# Arduino.net
KiCad netlist of a schematic drawn in Altium Designer
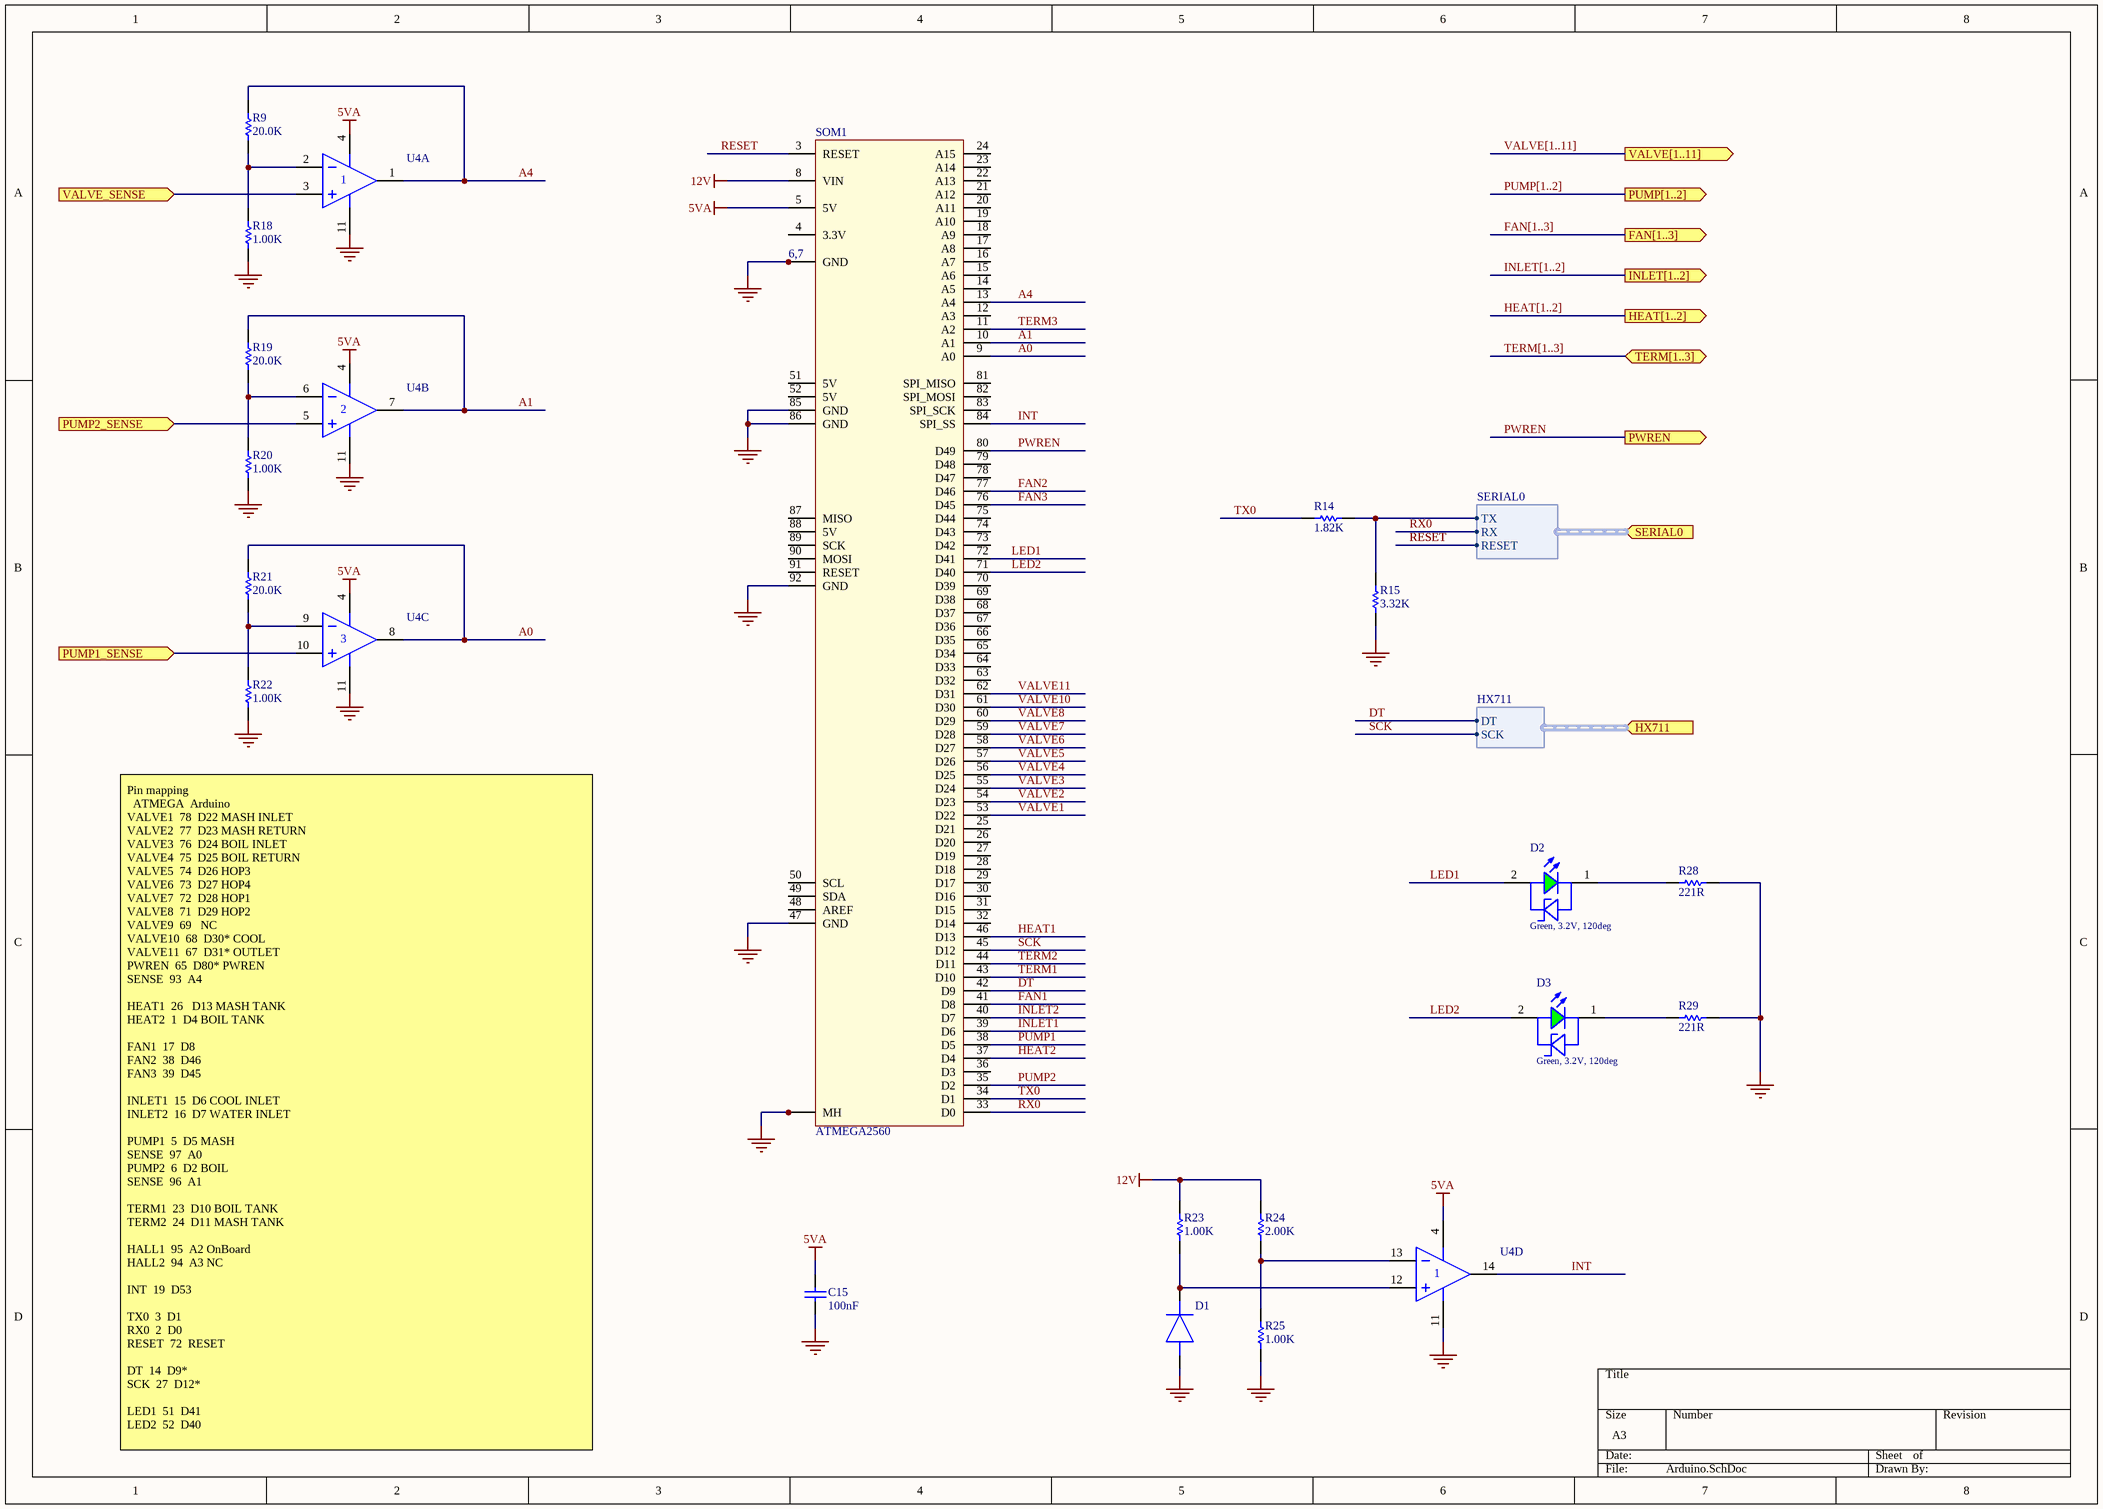
[diagram p0: Arduino.SchDoc]

(export (version "E")
  (design (tool "Eeschema 10.0.6"))
  (components
    (comp (ref "C15")
      (value "100nF")
      (footprint "CAP_0603_H090 (_IPC_MD)")
      (description "CAP CER 100NF 50V X7R 0603")
      (fields (field (name "PART NUMBER") "CL10B104KB8NNNC") (field (name "Comment") "100nF 0603"))
      (libsource (lib "MUAB_Altium_Lib") (part "CAP"))
    )
    (comp (ref "D1")
      (value "LL4148-GS18")
      (footprint "OpenBrewie:SOD-80")
      (description "Diode")
      (fields (field (name "MOUSER PART NUMBER") "78-LL4148-GS18"))
      (libsource (lib "OpenBrewie") (part "LL4148-GS18"))
    )
    (comp (ref "D2")
      (value "Green, 3.2V, 120deg")
      (footprint "WL-SMCC_0603_GS_BS")
      (description "WL-SMCC SMD Mono-color Chip LED Compact, size 0603, Green, 3.2V, 120deg")
      (fields (field (name "PART NUMBER") "150060GS73220") (field (name "PUBLISHER") "Wurth Elektronik"))
      (libsource (lib "Altium_WL-SMCC (rev19a)") (part "150060GS73220"))
    )
    (comp (ref "D3")
      (value "Green, 3.2V, 120deg")
      (footprint "WL-SMCC_0603_GS_BS")
      (description "WL-SMCC SMD Mono-color Chip LED Compact, size 0603, Green, 3.2V, 120deg")
      (fields (field (name "PART NUMBER") "150060GS73220") (field (name "PUBLISHER") "Wurth Elektronik"))
      (libsource (lib "Altium_WL-SMCC (rev19a)") (part "150060GS73220"))
    )
    (comp (ref "R9")
      (value "20.0K")
      (footprint "RES_0603_H050 (_IPC_MD)")
      (description "20.0K 1% 0,1W 75V 0603")
      (fields (field (name "PART NUMBER") "RES20.0K1%0603"))
      (libsource (lib "MUAB_Altium_Lib") (part "RES"))
    )
    (comp (ref "R14")
      (value "1.82K")
      (footprint "RES_0603_H050 (_IPC_MD)")
      (description "1.82K 1% 0,1W 75V 0603")
      (fields (field (name "PART NUMBER") "RES1.82K1%0603"))
      (libsource (lib "MUAB_Altium_Lib") (part "RES"))
    )
    (comp (ref "R15")
      (value "3.32K")
      (footprint "RES_0603_H050 (_IPC_MD)")
      (description "3.32K 1% 0,1W 75V 0603")
      (fields (field (name "PART NUMBER") "RES3.32K1%0603"))
      (libsource (lib "MUAB_Altium_Lib") (part "RES"))
    )
    (comp (ref "R18")
      (value "1.00K")
      (footprint "RES_0603_H050 (_IPC_MD)")
      (description "1.00K 1% 0,1W 75V 0603")
      (fields (field (name "PART NUMBER") "RES1.00K1%0603"))
      (libsource (lib "MUAB_Altium_Lib") (part "RES"))
    )
    (comp (ref "R19")
      (value "20.0K")
      (footprint "RES_0603_H050 (_IPC_MD)")
      (description "20.0K 1% 0,1W 75V 0603")
      (fields (field (name "PART NUMBER") "RES20.0K1%0603"))
      (libsource (lib "MUAB_Altium_Lib") (part "RES"))
    )
    (comp (ref "R20")
      (value "1.00K")
      (footprint "RES_0603_H050 (_IPC_MD)")
      (description "1.00K 1% 0,1W 75V 0603")
      (fields (field (name "PART NUMBER") "RES1.00K1%0603"))
      (libsource (lib "MUAB_Altium_Lib") (part "RES"))
    )
    (comp (ref "R21")
      (value "20.0K")
      (footprint "RES_0603_H050 (_IPC_MD)")
      (description "20.0K 1% 0,1W 75V 0603")
      (fields (field (name "PART NUMBER") "RES20.0K1%0603"))
      (libsource (lib "MUAB_Altium_Lib") (part "RES"))
    )
    (comp (ref "R22")
      (value "1.00K")
      (footprint "RES_0603_H050 (_IPC_MD)")
      (description "1.00K 1% 0,1W 75V 0603")
      (fields (field (name "PART NUMBER") "RES1.00K1%0603"))
      (libsource (lib "MUAB_Altium_Lib") (part "RES"))
    )
    (comp (ref "R23")
      (value "1.00K")
      (footprint "RES_0603_H050 (_IPC_MD)")
      (description "1.00K 1% 0,1W 75V 0603")
      (fields (field (name "PART NUMBER") "RES1.00K1%0603"))
      (libsource (lib "MUAB_Altium_Lib") (part "RES"))
    )
    (comp (ref "R24")
      (value "2.00K")
      (footprint "RES_0603_H050 (_IPC_MD)")
      (description "2.00K 1% 0,1W 75V 0603")
      (fields (field (name "PART NUMBER") "RES2.00K1%0603"))
      (libsource (lib "MUAB_Altium_Lib") (part "RES"))
    )
    (comp (ref "R25")
      (value "1.00K")
      (footprint "RES_0603_H050 (_IPC_MD)")
      (description "1.00K 1% 0,1W 75V 0603")
      (fields (field (name "PART NUMBER") "RES1.00K1%0603"))
      (libsource (lib "MUAB_Altium_Lib") (part "RES"))
    )
    (comp (ref "R28")
      (value "221R")
      (footprint "RES_0603_H050 (_IPC_MD)")
      (description "221R 1% 0,1W 75V 0603")
      (fields (field (name "PART NUMBER") "RES221R1%0603"))
      (libsource (lib "MUAB_Altium_Lib") (part "RES"))
    )
    (comp (ref "R29")
      (value "221R")
      (footprint "RES_0603_H050 (_IPC_MD)")
      (description "221R 1% 0,1W 75V 0603")
      (fields (field (name "PART NUMBER") "RES221R1%0603"))
      (libsource (lib "MUAB_Altium_Lib") (part "RES"))
    )
    (comp (ref "SOM1")
      (value "ATMEGA2560")
      (footprint "ATMEGA2560")
      (libsource (lib "OpenBrewie") (part "ATMEGA2560"))
    )
    (comp (ref "U4")
      (value "MAX4478ASD+")
      (footprint "SOIC127P600X175-14N")
      (description "IC OPAMP GP 2 CIRCUIT 8SOIC")
      (libsource (lib "MUAB_Altium_Lib") (part "MAX4478"))
    )
  )
  (nets
    (net (code "4") (name "/A0") (class "Default")
      (node (ref "R21") (pin "2") (pinfunction "2_2") (pintype "passive"))
      (node (ref "SOM1") (pin "9") (pinfunction "A0_9") (pintype "passive"))
      (node (ref "U4") (pin "8") (pinfunction "OUT3_8") (pintype "passive"))
    )
    (net (code "5") (name "/A1") (class "Default")
      (node (ref "R19") (pin "2") (pinfunction "2_2") (pintype "passive"))
      (node (ref "SOM1") (pin "10") (pinfunction "A1_10") (pintype "passive"))
      (node (ref "U4") (pin "7") (pinfunction "OUT2_7") (pintype "passive"))
    )
    (net (code "6") (name "/A4") (class "Default")
      (node (ref "R9") (pin "2") (pinfunction "2_2") (pintype "passive"))
      (node (ref "SOM1") (pin "13") (pinfunction "A4_13") (pintype "passive"))
      (node (ref "U4") (pin "1") (pinfunction "OUT1_1") (pintype "passive"))
    )
    (net (code "7") (name "/DT") (class "Default")
      (node (ref "SOM1") (pin "42") (pinfunction "D9_42") (pintype "passive"))
    )
    (net (code "8") (name "/FAN1") (class "Default")
      (node (ref "SOM1") (pin "41") (pinfunction "D8_41") (pintype "passive"))
    )
    (net (code "9") (name "/FAN2") (class "Default")
      (node (ref "SOM1") (pin "77") (pinfunction "D46_77") (pintype "passive"))
    )
    (net (code "10") (name "/FAN3") (class "Default")
      (node (ref "SOM1") (pin "76") (pinfunction "D45_76") (pintype "passive"))
    )
    (net (code "12") (name "/HEAT1") (class "Default")
      (node (ref "SOM1") (pin "46") (pinfunction "D13_46") (pintype "passive"))
    )
    (net (code "13") (name "/HEAT2") (class "Default")
      (node (ref "SOM1") (pin "37") (pinfunction "D4_37") (pintype "passive"))
    )
    (net (code "15") (name "/INLET1") (class "Default")
      (node (ref "SOM1") (pin "39") (pinfunction "D6_39") (pintype "passive"))
    )
    (net (code "16") (name "/INLET2") (class "Default")
      (node (ref "SOM1") (pin "40") (pinfunction "D7_40") (pintype "passive"))
    )
    (net (code "18") (name "/INT") (class "Default")
      (node (ref "SOM1") (pin "84") (pinfunction "SPI_SS_84") (pintype "passive"))
      (node (ref "U4") (pin "14") (pinfunction "OUT4_14") (pintype "passive"))
    )
    (net (code "19") (name "/LED1") (class "Default")
      (node (ref "D2") (pin "2") (pinfunction "A_2") (pintype "passive"))
      (node (ref "SOM1") (pin "72") (pinfunction "D41_72") (pintype "passive"))
    )
    (net (code "20") (name "/LED2") (class "Default")
      (node (ref "D3") (pin "2") (pinfunction "A_2") (pintype "passive"))
      (node (ref "SOM1") (pin "71") (pinfunction "D40_71") (pintype "passive"))
    )
    (net (code "21") (name "/PUMP1") (class "Default")
      (node (ref "SOM1") (pin "38") (pinfunction "D5_38") (pintype "passive"))
    )
    (net (code "22") (name "/PUMP1_SENSE") (class "Default")
      (node (ref "U4") (pin "10") (pinfunction "IN3+_10") (pintype "passive"))
    )
    (net (code "23") (name "/PUMP2") (class "Default")
      (node (ref "SOM1") (pin "35") (pinfunction "D2_35") (pintype "passive"))
    )
    (net (code "24") (name "/PUMP2_SENSE") (class "Default")
      (node (ref "U4") (pin "5") (pinfunction "IN2+_5") (pintype "passive"))
    )
    (net (code "26") (name "/PWREN") (class "Default")
      (node (ref "SOM1") (pin "80") (pinfunction "D49_80") (pintype "passive"))
    )
    (net (code "27") (name "/RESET") (class "Default")
      (node (ref "SOM1") (pin "3") (pinfunction "RESET_3") (pintype "passive"))
    )
    (net (code "28") (name "/RX0") (class "Default")
      (node (ref "SOM1") (pin "33") (pinfunction "D0_33") (pintype "passive"))
    )
    (net (code "29") (name "/SCK") (class "Default")
      (node (ref "SOM1") (pin "45") (pinfunction "D12_45") (pintype "passive"))
    )
    (net (code "30") (name "/TERM1") (class "Default")
      (node (ref "SOM1") (pin "43") (pinfunction "D10_43") (pintype "passive"))
    )
    (net (code "31") (name "/TERM2") (class "Default")
      (node (ref "SOM1") (pin "44") (pinfunction "D11_44") (pintype "passive"))
    )
    (net (code "32") (name "/TERM3") (class "Default")
      (node (ref "SOM1") (pin "11") (pinfunction "A2_11") (pintype "passive"))
    )
    (net (code "34") (name "/TX0") (class "Default")
      (node (ref "R14") (pin "1") (pinfunction "1_1") (pintype "passive"))
      (node (ref "SOM1") (pin "34") (pinfunction "D1_34") (pintype "passive"))
    )
    (net (code "35") (name "/VALVE1") (class "Default")
      (node (ref "SOM1") (pin "53") (pinfunction "D22_53") (pintype "passive"))
    )
    (net (code "36") (name "/VALVE2") (class "Default")
      (node (ref "SOM1") (pin "54") (pinfunction "D23_54") (pintype "passive"))
    )
    (net (code "37") (name "/VALVE3") (class "Default")
      (node (ref "SOM1") (pin "55") (pinfunction "D24_55") (pintype "passive"))
    )
    (net (code "38") (name "/VALVE4") (class "Default")
      (node (ref "SOM1") (pin "56") (pinfunction "D25_56") (pintype "passive"))
    )
    (net (code "39") (name "/VALVE5") (class "Default")
      (node (ref "SOM1") (pin "57") (pinfunction "D26_57") (pintype "passive"))
    )
    (net (code "40") (name "/VALVE6") (class "Default")
      (node (ref "SOM1") (pin "58") (pinfunction "D27_58") (pintype "passive"))
    )
    (net (code "41") (name "/VALVE7") (class "Default")
      (node (ref "SOM1") (pin "59") (pinfunction "D28_59") (pintype "passive"))
    )
    (net (code "42") (name "/VALVE8") (class "Default")
      (node (ref "SOM1") (pin "60") (pinfunction "D29_60") (pintype "passive"))
    )
    (net (code "43") (name "/VALVE10") (class "Default")
      (node (ref "SOM1") (pin "61") (pinfunction "D30_61") (pintype "passive"))
    )
    (net (code "44") (name "/VALVE11") (class "Default")
      (node (ref "SOM1") (pin "62") (pinfunction "D31_62") (pintype "passive"))
    )
    (net (code "46") (name "/VALVE_SENSE") (class "Default")
      (node (ref "U4") (pin "3") (pinfunction "IN1+_3") (pintype "passive"))
    )
    (net (code "49") (name "5VA") (class "Default")
      (node (ref "C15") (pin "1") (pinfunction "1_1") (pintype "passive"))
      (node (ref "SOM1") (pin "5") (pinfunction "5V_5") (pintype "power_in"))
      (node (ref "U4") (pin "4") (pinfunction "V+_4") (pintype "power_in"))
    )
    (net (code "50") (name "12V") (class "Default")
      (node (ref "R23") (pin "1") (pinfunction "1_1") (pintype "passive"))
      (node (ref "R24") (pin "1") (pinfunction "1_1") (pintype "passive"))
      (node (ref "SOM1") (pin "8") (pinfunction "VIN_8") (pintype "power_in"))
    )
    (net (code "51") (name "GND") (class "Default")
      (node (ref "C15") (pin "2") (pinfunction "2_2") (pintype "passive"))
      (node (ref "D1") (pin "2") (pinfunction "A_2") (pintype "passive"))
      (node (ref "R15") (pin "2") (pinfunction "2_2") (pintype "passive"))
      (node (ref "R18") (pin "1") (pinfunction "1_1") (pintype "passive"))
      (node (ref "R20") (pin "1") (pinfunction "1_1") (pintype "passive"))
      (node (ref "R22") (pin "1") (pinfunction "1_1") (pintype "passive"))
      (node (ref "R25") (pin "2") (pinfunction "2_2") (pintype "passive"))
      (node (ref "R28") (pin "2") (pinfunction "2_2") (pintype "passive"))
      (node (ref "R29") (pin "2") (pinfunction "2_2") (pintype "passive"))
      (node (ref "SOM1") (pin "47") (pinfunction "GND_47") (pintype "power_in"))
      (node (ref "SOM1") (pin "6") (pinfunction "GND_6") (pintype "power_in"))
      (node (ref "SOM1") (pin "7") (pinfunction "GND_7") (pintype "power_in"))
      (node (ref "SOM1") (pin "85") (pinfunction "GND_85") (pintype "power_in"))
      (node (ref "SOM1") (pin "86") (pinfunction "GND_86") (pintype "power_in"))
      (node (ref "SOM1") (pin "92") (pinfunction "GND_92") (pintype "power_in"))
      (node (ref "SOM1") (pin "MH1") (pinfunction "MH_MH1") (pintype "passive"))
      (node (ref "SOM1") (pin "MH2") (pinfunction "MH_MH2") (pintype "passive"))
      (node (ref "SOM1") (pin "MH3") (pinfunction "MH_MH3") (pintype "passive"))
      (node (ref "SOM1") (pin "MH4") (pinfunction "MH_MH4") (pintype "passive"))
      (node (ref "SOM1") (pin "MH5") (pinfunction "MH_MH5") (pintype "passive"))
      (node (ref "U4") (pin "11") (pinfunction "V-_11") (pintype "power_in"))
    )
    (net (code "52") (name "Net-(D1-K)") (class "Default")
      (node (ref "D1") (pin "1") (pinfunction "K_1") (pintype "passive"))
      (node (ref "R23") (pin "2") (pinfunction "2_2") (pintype "passive"))
      (node (ref "U4") (pin "12") (pinfunction "IN4+_12") (pintype "passive"))
    )
    (net (code "53") (name "Net-(D2-K)") (class "Default")
      (node (ref "D2") (pin "1") (pinfunction "K_1") (pintype "passive"))
      (node (ref "R28") (pin "1") (pinfunction "1_1") (pintype "passive"))
    )
    (net (code "54") (name "Net-(D3-K)") (class "Default")
      (node (ref "D3") (pin "1") (pinfunction "K_1") (pintype "passive"))
      (node (ref "R29") (pin "1") (pinfunction "1_1") (pintype "passive"))
    )
    (net (code "55") (name "Net-(R14-Pad2)") (class "Default")
      (node (ref "R14") (pin "2") (pinfunction "2_2") (pintype "passive"))
      (node (ref "R15") (pin "1") (pinfunction "1_1") (pintype "passive"))
    )
    (net (code "56") (name "Net-(U4A-IN1-)") (class "Default")
      (node (ref "R18") (pin "2") (pinfunction "2_2") (pintype "passive"))
      (node (ref "R9") (pin "1") (pinfunction "1_1") (pintype "passive"))
      (node (ref "U4") (pin "2") (pinfunction "IN1-_2") (pintype "passive"))
    )
    (net (code "57") (name "Net-(U4B-IN2-)") (class "Default")
      (node (ref "R19") (pin "1") (pinfunction "1_1") (pintype "passive"))
      (node (ref "R20") (pin "2") (pinfunction "2_2") (pintype "passive"))
      (node (ref "U4") (pin "6") (pinfunction "IN2-_6") (pintype "passive"))
    )
    (net (code "58") (name "Net-(U4C-IN3-)") (class "Default")
      (node (ref "R21") (pin "1") (pinfunction "1_1") (pintype "passive"))
      (node (ref "R22") (pin "2") (pinfunction "2_2") (pintype "passive"))
      (node (ref "U4") (pin "9") (pinfunction "IN3-_9") (pintype "passive"))
    )
    (net (code "59") (name "Net-(U4D-IN4-)") (class "Default")
      (node (ref "R24") (pin "2") (pinfunction "2_2") (pintype "passive"))
      (node (ref "R25") (pin "1") (pinfunction "1_1") (pintype "passive"))
      (node (ref "U4") (pin "13") (pinfunction "IN4-_13") (pintype "passive"))
    )
    (net (code "60") (name "unconnected-(SOM1-3.3V-Pad4)") (class "Default")
      (node (ref "SOM1") (pin "4") (pinfunction "3.3V_4") (pintype "power_in"))
    )
    (net (code "61") (name "unconnected-(SOM1-5V-Pad51)") (class "Default")
      (node (ref "SOM1") (pin "51") (pinfunction "5V_51") (pintype "power_in"))
    )
    (net (code "62") (name "unconnected-(SOM1-5V-Pad52)") (class "Default")
      (node (ref "SOM1") (pin "52") (pinfunction "5V_52") (pintype "power_in"))
    )
    (net (code "63") (name "unconnected-(SOM1-5V-Pad88)") (class "Default")
      (node (ref "SOM1") (pin "88") (pinfunction "5V_88") (pintype "power_in"))
    )
    (net (code "64") (name "unconnected-(SOM1-A3-Pad12)") (class "Default")
      (node (ref "SOM1") (pin "12") (pinfunction "A3_12") (pintype "passive"))
    )
    (net (code "65") (name "unconnected-(SOM1-A5-Pad14)") (class "Default")
      (node (ref "SOM1") (pin "14") (pinfunction "A5_14") (pintype "passive"))
    )
    (net (code "66") (name "unconnected-(SOM1-A6-Pad15)") (class "Default")
      (node (ref "SOM1") (pin "15") (pinfunction "A6_15") (pintype "passive"))
    )
    (net (code "67") (name "unconnected-(SOM1-A7-Pad16)") (class "Default")
      (node (ref "SOM1") (pin "16") (pinfunction "A7_16") (pintype "passive"))
    )
    (net (code "68") (name "unconnected-(SOM1-A8-Pad17)") (class "Default")
      (node (ref "SOM1") (pin "17") (pinfunction "A8_17") (pintype "passive"))
    )
    (net (code "69") (name "unconnected-(SOM1-A9-Pad18)") (class "Default")
      (node (ref "SOM1") (pin "18") (pinfunction "A9_18") (pintype "passive"))
    )
    (net (code "70") (name "unconnected-(SOM1-A10-Pad19)") (class "Default")
      (node (ref "SOM1") (pin "19") (pinfunction "A10_19") (pintype "passive"))
    )
    (net (code "71") (name "unconnected-(SOM1-A11-Pad20)") (class "Default")
      (node (ref "SOM1") (pin "20") (pinfunction "A11_20") (pintype "passive"))
    )
    (net (code "72") (name "unconnected-(SOM1-A12-Pad21)") (class "Default")
      (node (ref "SOM1") (pin "21") (pinfunction "A12_21") (pintype "passive"))
    )
    (net (code "73") (name "unconnected-(SOM1-A13-Pad22)") (class "Default")
      (node (ref "SOM1") (pin "22") (pinfunction "A13_22") (pintype "passive"))
    )
    (net (code "74") (name "unconnected-(SOM1-A14-Pad23)") (class "Default")
      (node (ref "SOM1") (pin "23") (pinfunction "A14_23") (pintype "passive"))
    )
    (net (code "75") (name "unconnected-(SOM1-A15-Pad24)") (class "Default")
      (node (ref "SOM1") (pin "24") (pinfunction "A15_24") (pintype "passive"))
    )
    (net (code "76") (name "unconnected-(SOM1-AREF-Pad48)") (class "Default")
      (node (ref "SOM1") (pin "48") (pinfunction "AREF_48") (pintype "passive"))
    )
    (net (code "77") (name "unconnected-(SOM1-D3-Pad36)") (class "Default")
      (node (ref "SOM1") (pin "36") (pinfunction "D3_36") (pintype "passive"))
    )
    (net (code "78") (name "unconnected-(SOM1-D14-Pad32)") (class "Default")
      (node (ref "SOM1") (pin "32") (pinfunction "D14_32") (pintype "passive"))
    )
    (net (code "79") (name "unconnected-(SOM1-D15-Pad31)") (class "Default")
      (node (ref "SOM1") (pin "31") (pinfunction "D15_31") (pintype "passive"))
    )
    (net (code "80") (name "unconnected-(SOM1-D16-Pad30)") (class "Default")
      (node (ref "SOM1") (pin "30") (pinfunction "D16_30") (pintype "passive"))
    )
    (net (code "81") (name "unconnected-(SOM1-D17-Pad29)") (class "Default")
      (node (ref "SOM1") (pin "29") (pinfunction "D17_29") (pintype "passive"))
    )
    (net (code "82") (name "unconnected-(SOM1-D18-Pad28)") (class "Default")
      (node (ref "SOM1") (pin "28") (pinfunction "D18_28") (pintype "passive"))
    )
    (net (code "83") (name "unconnected-(SOM1-D19-Pad27)") (class "Default")
      (node (ref "SOM1") (pin "27") (pinfunction "D19_27") (pintype "passive"))
    )
    (net (code "84") (name "unconnected-(SOM1-D20-Pad26)") (class "Default")
      (node (ref "SOM1") (pin "26") (pinfunction "D20_26") (pintype "passive"))
    )
    (net (code "85") (name "unconnected-(SOM1-D21-Pad25)") (class "Default")
      (node (ref "SOM1") (pin "25") (pinfunction "D21_25") (pintype "passive"))
    )
    (net (code "86") (name "unconnected-(SOM1-D32-Pad63)") (class "Default")
      (node (ref "SOM1") (pin "63") (pinfunction "D32_63") (pintype "passive"))
    )
    (net (code "87") (name "unconnected-(SOM1-D33-Pad64)") (class "Default")
      (node (ref "SOM1") (pin "64") (pinfunction "D33_64") (pintype "passive"))
    )
    (net (code "88") (name "unconnected-(SOM1-D34-Pad65)") (class "Default")
      (node (ref "SOM1") (pin "65") (pinfunction "D34_65") (pintype "passive"))
    )
    (net (code "89") (name "unconnected-(SOM1-D35-Pad66)") (class "Default")
      (node (ref "SOM1") (pin "66") (pinfunction "D35_66") (pintype "passive"))
    )
    (net (code "90") (name "unconnected-(SOM1-D36-Pad67)") (class "Default")
      (node (ref "SOM1") (pin "67") (pinfunction "D36_67") (pintype "passive"))
    )
    (net (code "91") (name "unconnected-(SOM1-D37-Pad68)") (class "Default")
      (node (ref "SOM1") (pin "68") (pinfunction "D37_68") (pintype "passive"))
    )
    (net (code "92") (name "unconnected-(SOM1-D38-Pad69)") (class "Default")
      (node (ref "SOM1") (pin "69") (pinfunction "D38_69") (pintype "passive"))
    )
    (net (code "93") (name "unconnected-(SOM1-D39-Pad70)") (class "Default")
      (node (ref "SOM1") (pin "70") (pinfunction "D39_70") (pintype "passive"))
    )
    (net (code "94") (name "unconnected-(SOM1-D42-Pad73)") (class "Default")
      (node (ref "SOM1") (pin "73") (pinfunction "D42_73") (pintype "passive"))
    )
    (net (code "95") (name "unconnected-(SOM1-D43-Pad74)") (class "Default")
      (node (ref "SOM1") (pin "74") (pinfunction "D43_74") (pintype "passive"))
    )
    (net (code "96") (name "unconnected-(SOM1-D44-Pad75)") (class "Default")
      (node (ref "SOM1") (pin "75") (pinfunction "D44_75") (pintype "passive"))
    )
    (net (code "97") (name "unconnected-(SOM1-D47-Pad78)") (class "Default")
      (node (ref "SOM1") (pin "78") (pinfunction "D47_78") (pintype "passive"))
    )
    (net (code "98") (name "unconnected-(SOM1-D48-Pad79)") (class "Default")
      (node (ref "SOM1") (pin "79") (pinfunction "D48_79") (pintype "passive"))
    )
    (net (code "99") (name "unconnected-(SOM1-MISO-Pad87)") (class "Default")
      (node (ref "SOM1") (pin "87") (pinfunction "MISO_87") (pintype "passive"))
    )
    (net (code "100") (name "unconnected-(SOM1-MOSI-Pad90)") (class "Default")
      (node (ref "SOM1") (pin "90") (pinfunction "MOSI_90") (pintype "passive"))
    )
    (net (code "101") (name "unconnected-(SOM1-RESET-Pad91)") (class "Default")
      (node (ref "SOM1") (pin "91") (pinfunction "RESET_91") (pintype "passive"))
    )
    (net (code "102") (name "unconnected-(SOM1-SCK-Pad89)") (class "Default")
      (node (ref "SOM1") (pin "89") (pinfunction "SCK_89") (pintype "passive"))
    )
    (net (code "103") (name "unconnected-(SOM1-SCL-Pad50)") (class "Default")
      (node (ref "SOM1") (pin "50") (pinfunction "SCL_50") (pintype "passive"))
    )
    (net (code "104") (name "unconnected-(SOM1-SDA-Pad49)") (class "Default")
      (node (ref "SOM1") (pin "49") (pinfunction "SDA_49") (pintype "passive"))
    )
    (net (code "105") (name "unconnected-(SOM1-SPI_MISO-Pad81)") (class "Default")
      (node (ref "SOM1") (pin "81") (pinfunction "SPI_MISO_81") (pintype "passive"))
    )
    (net (code "106") (name "unconnected-(SOM1-SPI_MOSI-Pad82)") (class "Default")
      (node (ref "SOM1") (pin "82") (pinfunction "SPI_MOSI_82") (pintype "passive"))
    )
    (net (code "107") (name "unconnected-(SOM1-SPI_SCK-Pad83)") (class "Default")
      (node (ref "SOM1") (pin "83") (pinfunction "SPI_SCK_83") (pintype "passive"))
    )
    (net (code "108") (name "unconnected-(U4A-V+-Pad4)") (class "Default")
      (node (ref "U4") (pin "4") (pinfunction "V+_4") (pintype "power_in"))
    )
    (net (code "109") (name "unconnected-(U4B-V+-Pad4)") (class "Default")
      (node (ref "U4") (pin "4") (pinfunction "V+_4") (pintype "power_in"))
    )
    (net (code "110") (name "unconnected-(U4C-V+-Pad4)") (class "Default")
      (node (ref "U4") (pin "4") (pinfunction "V+_4") (pintype "power_in"))
    )
  )
)
